# Op-amp_Microphone_Preamp.net
KiCad netlist of a schematic drawn in EAGLE
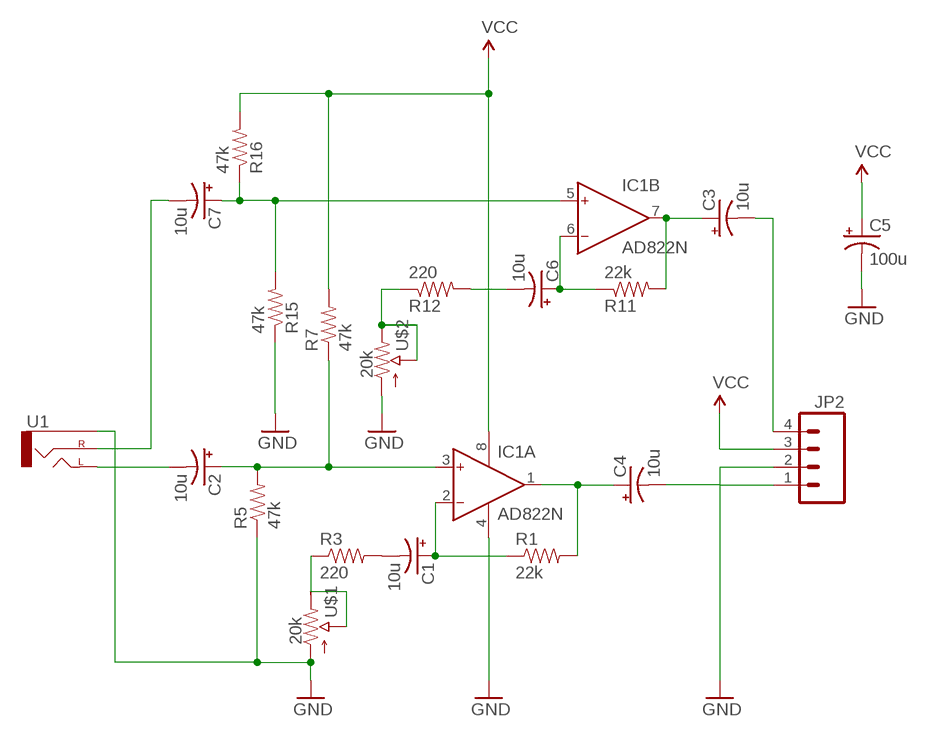
[diagram p0: schematic, sheet 1]

(export (version "E")
  (design (tool "Eeschema 10.0.6"))
  (components
    (comp (ref "C1")
      (value "10u")
      (footprint "eagle-import:CPOL-RADIAL-100UF-25V")
      (libsource (lib "eagle-import") (part "CAP_POLPTH1"))
    )
    (comp (ref "C2")
      (value "10u")
      (footprint "eagle-import:CPOL-RADIAL-100UF-25V")
      (libsource (lib "eagle-import") (part "CAP_POLPTH1"))
    )
    (comp (ref "C3")
      (value "10u")
      (footprint "eagle-import:CPOL-RADIAL-100UF-25V")
      (libsource (lib "eagle-import") (part "CAP_POLPTH1"))
    )
    (comp (ref "C4")
      (value "10u")
      (footprint "eagle-import:CPOL-RADIAL-100UF-25V")
      (libsource (lib "eagle-import") (part "CAP_POLPTH1"))
    )
    (comp (ref "C5")
      (value "100u")
      (footprint "eagle-import:CPOL-RADIAL-100UF-25V")
      (libsource (lib "eagle-import") (part "CAP_POLPTH1"))
    )
    (comp (ref "C6")
      (value "10u")
      (footprint "eagle-import:CPOL-RADIAL-100UF-25V")
      (libsource (lib "eagle-import") (part "CAP_POLPTH1"))
    )
    (comp (ref "C7")
      (value "10u")
      (footprint "eagle-import:CPOL-RADIAL-100UF-25V")
      (libsource (lib "eagle-import") (part "CAP_POLPTH1"))
    )
    (comp (ref "IC1")
      (value "AD822N")
      (footprint "eagle-import:DIL08")
      (libsource (lib "eagle-import") (part "AD822N"))
    )
    (comp (ref "JP2")
      (value "M04POLAR")
      (footprint "eagle-import:MOLEX-1X4")
      (libsource (lib "eagle-import") (part "M04POLAR"))
    )
    (comp (ref "R1")
      (value "22k")
      (footprint "eagle-import:1_6W-RES")
      (libsource (lib "eagle-import") (part "RESISTORPTH-1/6W"))
    )
    (comp (ref "R3")
      (value "220")
      (footprint "eagle-import:AXIAL-0.4")
      (libsource (lib "eagle-import") (part "SparkFun_RESISTORPTH-1/4W"))
    )
    (comp (ref "R5")
      (value "47k")
      (footprint "eagle-import:AXIAL-0.4")
      (libsource (lib "eagle-import") (part "SparkFun_RESISTORPTH-1/4W"))
    )
    (comp (ref "R7")
      (value "47k")
      (footprint "eagle-import:AXIAL-0.4")
      (libsource (lib "eagle-import") (part "SparkFun_RESISTORPTH-1/4W"))
    )
    (comp (ref "R11")
      (value "22k")
      (footprint "eagle-import:1_6W-RES")
      (libsource (lib "eagle-import") (part "SparkFun_RESISTORPTH-1/6W"))
    )
    (comp (ref "R12")
      (value "220")
      (footprint "eagle-import:AXIAL-0.4")
      (libsource (lib "eagle-import") (part "SparkFun_RESISTORPTH-1/4W"))
    )
    (comp (ref "R15")
      (value "47k")
      (footprint "eagle-import:AXIAL-0.4")
      (libsource (lib "eagle-import") (part "SparkFun_RESISTORPTH-1/4W"))
    )
    (comp (ref "R16")
      (value "47k")
      (footprint "eagle-import:AXIAL-0.4")
      (libsource (lib "eagle-import") (part "SparkFun_RESISTORPTH-1/4W"))
    )
    (comp (ref "U$1")
      (value "20k")
      (footprint "eagle-import:3362U")
      (libsource (lib "eagle-import") (part "POT100K_3362U"))
    )
    (comp (ref "U$2")
      (value "20k")
      (footprint "eagle-import:3362U")
      (libsource (lib "eagle-import") (part "POT100K_3362U"))
    )
    (comp (ref "U1")
      (value "AUDIO-JACKPTH")
      (footprint "eagle-import:AUDIO-JACK")
      (libsource (lib "eagle-import") (part "AUDIO-JACKPTH"))
    )
  )
  (nets
    (net (code "1") (name "GND") (class "Default")
      (node (ref "C5") (pin "2") (pinfunction "-_2") (pintype "passive"))
      (node (ref "IC1") (pin "4") (pinfunction "V-_4") (pintype "power_in"))
      (node (ref "JP2") (pin "2") (pinfunction "2_2") (pintype "passive"))
      (node (ref "R15") (pin "P$1") (pinfunction "1_P$1") (pintype "passive"))
      (node (ref "R5") (pin "P$1") (pinfunction "1_P$1") (pintype "passive"))
      (node (ref "U$1") (pin "P$3") (pinfunction "A_P$3") (pintype "passive"))
      (node (ref "U$2") (pin "P$3") (pinfunction "A_P$3") (pintype "passive"))
      (node (ref "U1") (pin "SLEEVE") (pinfunction "SLEEVE_SLEEVE") (pintype "bidirectional"))
    )
    (net (code "2") (name "Net-(C1-+)") (class "Default")
      (node (ref "C1") (pin "1") (pinfunction "+_1") (pintype "passive"))
      (node (ref "IC1") (pin "2") (pinfunction "IN-_2") (pintype "input"))
      (node (ref "R1") (pin "1") (pinfunction "1_1") (pintype "passive"))
    )
    (net (code "3") (name "Net-(C1--)") (class "Default")
      (node (ref "C1") (pin "2") (pinfunction "-_2") (pintype "passive"))
      (node (ref "R3") (pin "P$2") (pinfunction "2_P$2") (pintype "passive"))
    )
    (net (code "4") (name "Net-(C2-+)") (class "Default")
      (node (ref "C2") (pin "1") (pinfunction "+_1") (pintype "passive"))
      (node (ref "IC1") (pin "3") (pinfunction "IN+_3") (pintype "input"))
      (node (ref "R5") (pin "P$2") (pinfunction "2_P$2") (pintype "passive"))
      (node (ref "R7") (pin "P$1") (pinfunction "1_P$1") (pintype "passive"))
    )
    (net (code "5") (name "Net-(C2--)") (class "Default")
      (node (ref "C2") (pin "2") (pinfunction "-_2") (pintype "passive"))
      (node (ref "U1") (pin "TIP") (pinfunction "LEFT_TIP") (pintype "bidirectional"))
    )
    (net (code "6") (name "Net-(C3-+)") (class "Default")
      (node (ref "C3") (pin "1") (pinfunction "+_1") (pintype "passive"))
      (node (ref "IC1") (pin "7") (pinfunction "OUT_7") (pintype "output"))
      (node (ref "R11") (pin "2") (pinfunction "2_2") (pintype "passive"))
    )
    (net (code "7") (name "Net-(C3--)") (class "Default")
      (node (ref "C3") (pin "2") (pinfunction "-_2") (pintype "passive"))
      (node (ref "JP2") (pin "4") (pinfunction "4_4") (pintype "passive"))
    )
    (net (code "8") (name "Net-(C4-+)") (class "Default")
      (node (ref "C4") (pin "1") (pinfunction "+_1") (pintype "passive"))
      (node (ref "IC1") (pin "1") (pinfunction "OUT_1") (pintype "output"))
      (node (ref "R1") (pin "2") (pinfunction "2_2") (pintype "passive"))
    )
    (net (code "9") (name "Net-(C4--)") (class "Default")
      (node (ref "C4") (pin "2") (pinfunction "-_2") (pintype "passive"))
      (node (ref "JP2") (pin "1") (pinfunction "1_1") (pintype "passive"))
    )
    (net (code "10") (name "Net-(C6-+)") (class "Default")
      (node (ref "C6") (pin "1") (pinfunction "+_1") (pintype "passive"))
      (node (ref "IC1") (pin "6") (pinfunction "IN-_6") (pintype "input"))
      (node (ref "R11") (pin "1") (pinfunction "1_1") (pintype "passive"))
    )
    (net (code "11") (name "Net-(C6--)") (class "Default")
      (node (ref "C6") (pin "2") (pinfunction "-_2") (pintype "passive"))
      (node (ref "R12") (pin "P$2") (pinfunction "2_P$2") (pintype "passive"))
    )
    (net (code "12") (name "Net-(C7-+)") (class "Default")
      (node (ref "C7") (pin "1") (pinfunction "+_1") (pintype "passive"))
      (node (ref "IC1") (pin "5") (pinfunction "IN+_5") (pintype "input"))
      (node (ref "R15") (pin "P$2") (pinfunction "2_P$2") (pintype "passive"))
      (node (ref "R16") (pin "P$1") (pinfunction "1_P$1") (pintype "passive"))
    )
    (net (code "13") (name "Net-(C7--)") (class "Default")
      (node (ref "C7") (pin "2") (pinfunction "-_2") (pintype "passive"))
      (node (ref "U1") (pin "RING") (pinfunction "RIGHT_RING") (pintype "bidirectional"))
    )
    (net (code "14") (name "Net-(R3-1)") (class "Default")
      (node (ref "R3") (pin "P$1") (pinfunction "1_P$1") (pintype "passive"))
      (node (ref "U$1") (pin "P$1") (pinfunction "E_P$1") (pintype "passive"))
      (node (ref "U$1") (pin "P$2") (pinfunction "S_P$2") (pintype "passive"))
    )
    (net (code "15") (name "Net-(R12-1)") (class "Default")
      (node (ref "R12") (pin "P$1") (pinfunction "1_P$1") (pintype "passive"))
      (node (ref "U$2") (pin "P$1") (pinfunction "E_P$1") (pintype "passive"))
      (node (ref "U$2") (pin "P$2") (pinfunction "S_P$2") (pintype "passive"))
    )
    (net (code "16") (name "VCC") (class "Default")
      (node (ref "C5") (pin "1") (pinfunction "+_1") (pintype "passive"))
      (node (ref "IC1") (pin "8") (pinfunction "V+_8") (pintype "power_in"))
      (node (ref "JP2") (pin "3") (pinfunction "3_3") (pintype "passive"))
      (node (ref "R16") (pin "P$2") (pinfunction "2_P$2") (pintype "passive"))
      (node (ref "R7") (pin "P$2") (pinfunction "2_P$2") (pintype "passive"))
    )
  )
)
